# quadrotor.net
KiCad netlist of a schematic drawn in EAGLE
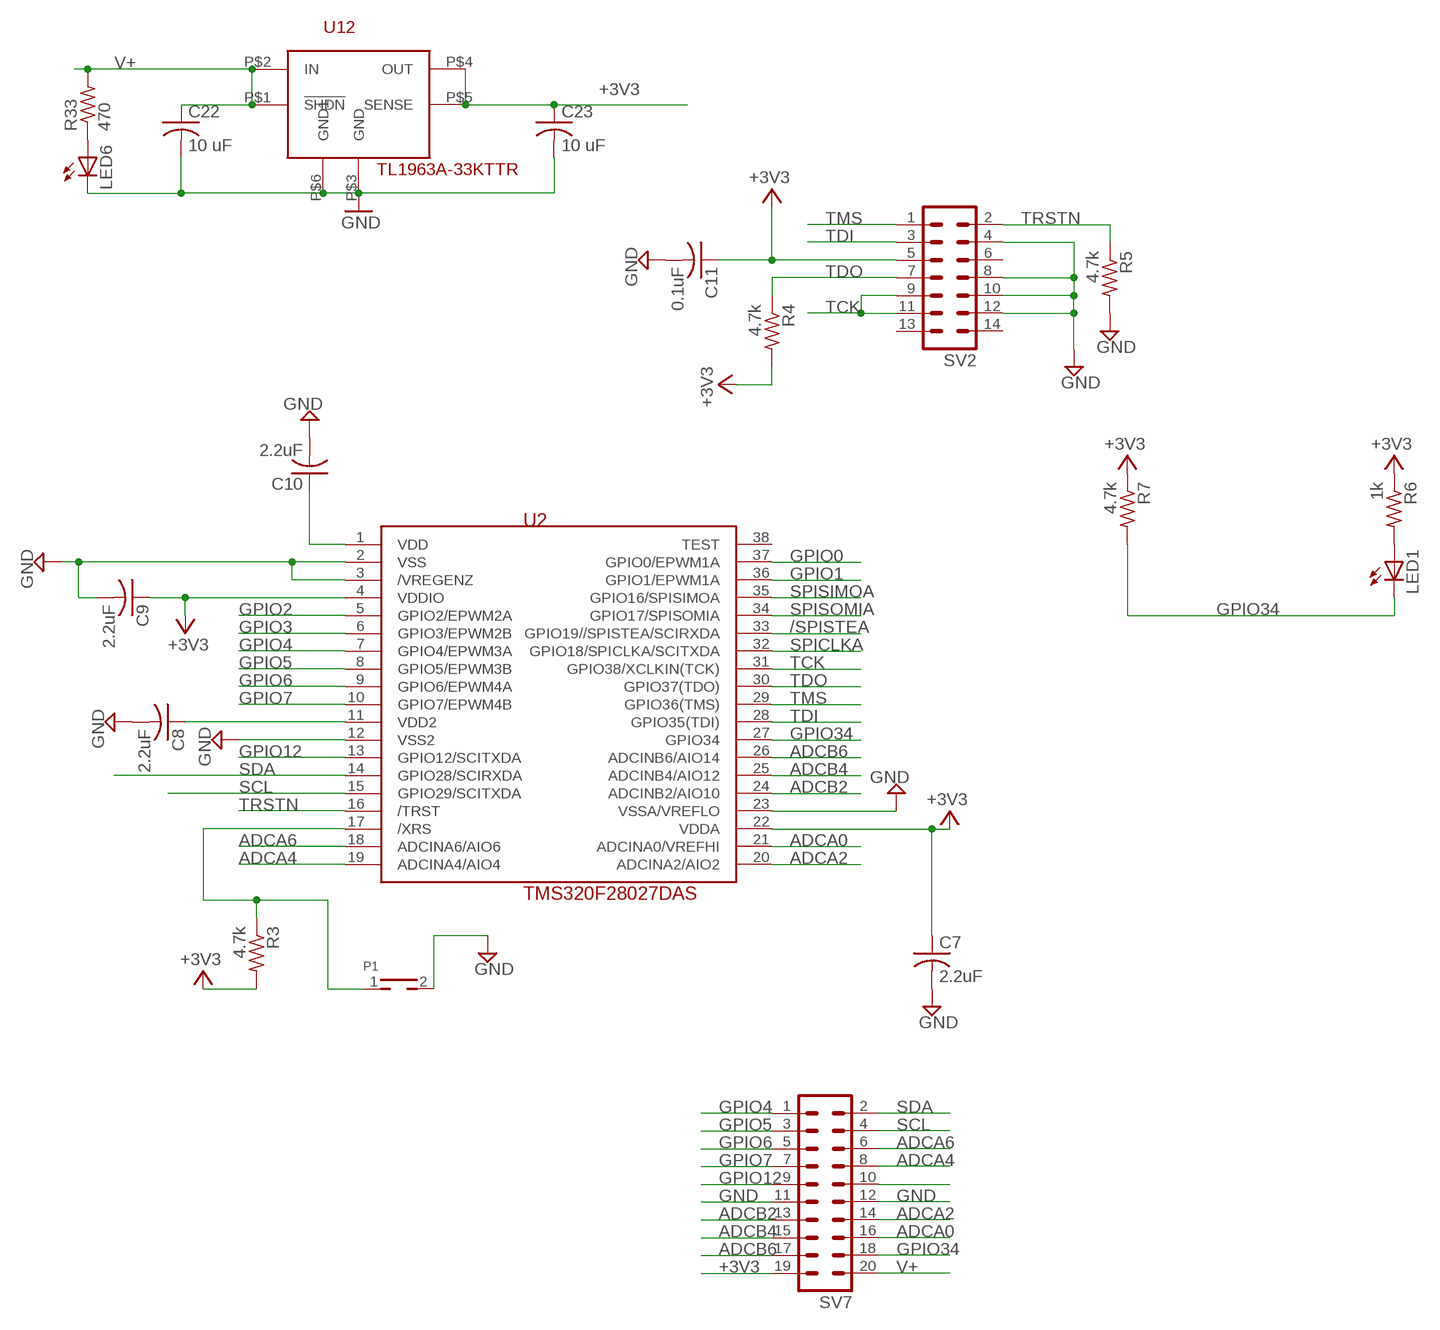
[diagram p0: schematic, sheet 1, part 1 of 2]
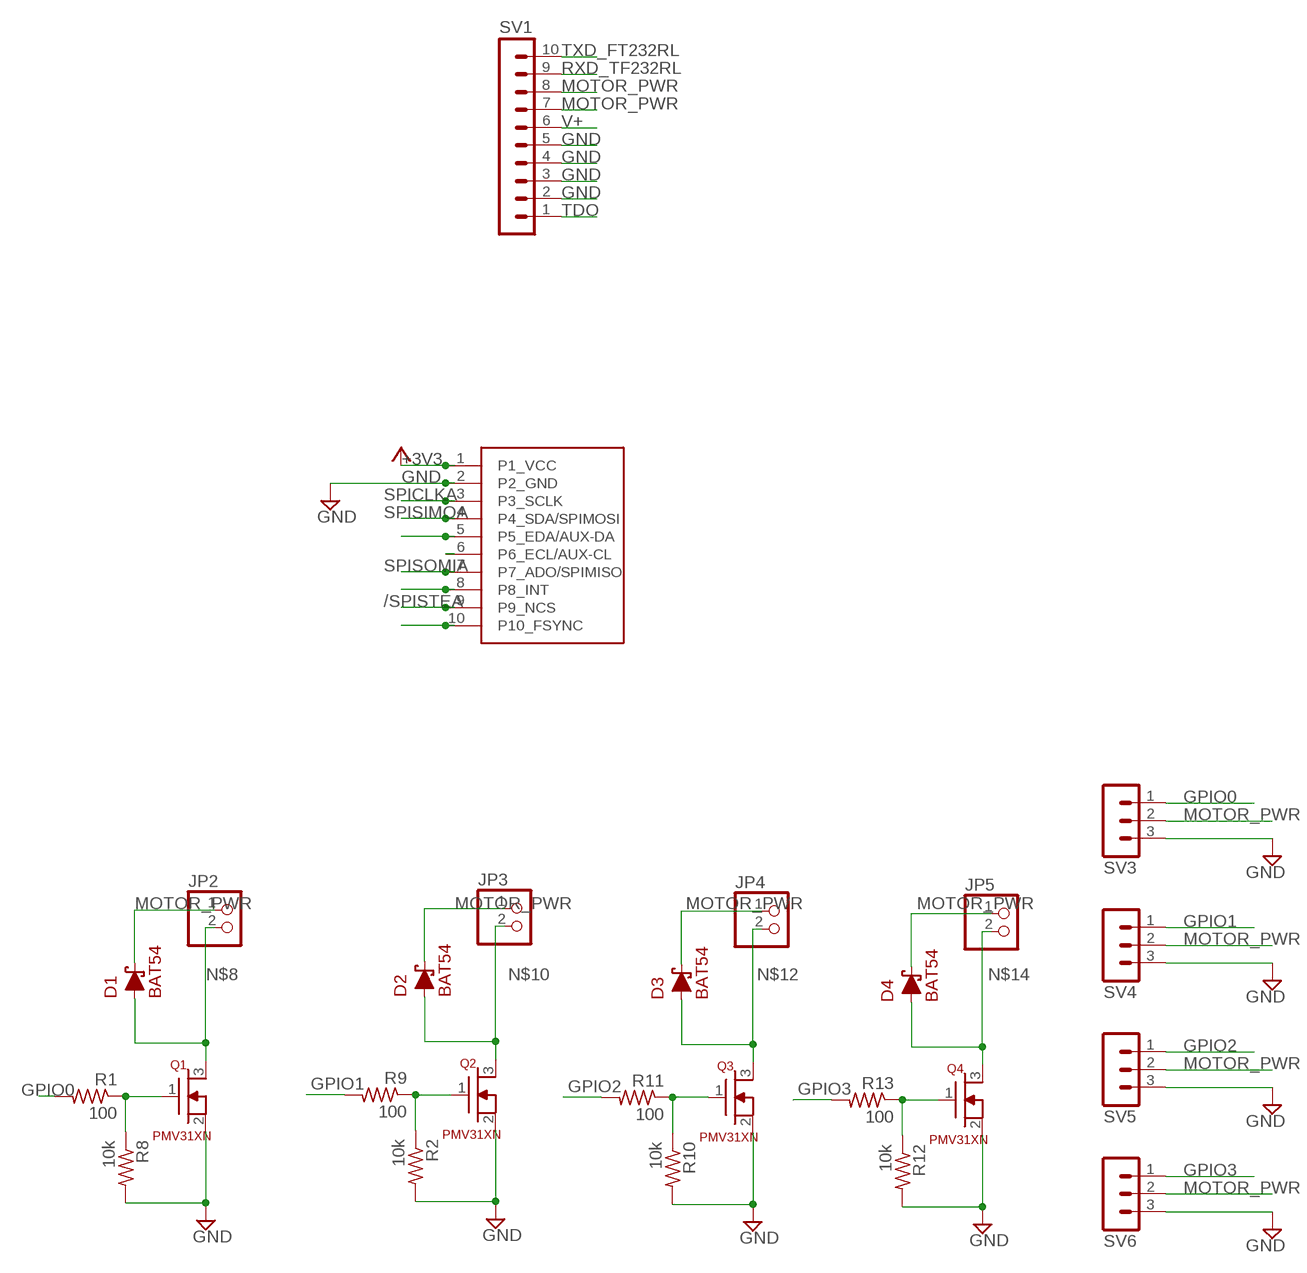
[diagram p1: schematic, sheet 1, part 2 of 2]

(export (version "E")
  (design (tool "Eeschema 10.0.6"))
  (components
    (comp (ref "C7")
      (value "2.2uF")
      (footprint "eagle-import:C1206")
      (libsource (lib "eagle-import") (part "C-USC1206"))
    )
    (comp (ref "C8")
      (value "2.2uF")
      (footprint "eagle-import:C1206")
      (libsource (lib "eagle-import") (part "C-USC1206"))
    )
    (comp (ref "C9")
      (value "2.2uF")
      (footprint "eagle-import:C1206")
      (libsource (lib "eagle-import") (part "C-USC1206"))
    )
    (comp (ref "C10")
      (value "2.2uF")
      (footprint "eagle-import:C1206")
      (libsource (lib "eagle-import") (part "C-USC1206"))
    )
    (comp (ref "C11")
      (value "0.1uF")
      (footprint "eagle-import:C1206")
      (libsource (lib "eagle-import") (part "C-USC1206"))
    )
    (comp (ref "C22")
      (value "10 uF")
      (footprint "eagle-import:C1206")
      (libsource (lib "eagle-import") (part "C-USC1206"))
    )
    (comp (ref "C23")
      (value "10 uF")
      (footprint "eagle-import:C1206")
      (libsource (lib "eagle-import") (part "C-USC1206"))
    )
    (comp (ref "D1")
      (value "BAT54")
      (footprint "eagle-import:SOT23")
      (libsource (lib "eagle-import") (part "BAT54"))
    )
    (comp (ref "D2")
      (value "BAT54")
      (footprint "eagle-import:SOT23")
      (libsource (lib "eagle-import") (part "BAT54"))
    )
    (comp (ref "D3")
      (value "BAT54")
      (footprint "eagle-import:SOT23")
      (libsource (lib "eagle-import") (part "BAT54"))
    )
    (comp (ref "D4")
      (value "BAT54")
      (footprint "eagle-import:SOT23")
      (libsource (lib "eagle-import") (part "BAT54"))
    )
    (comp (ref "JP2")
      (value "PINHD-1X2")
      (footprint "eagle-import:1X02")
      (libsource (lib "eagle-import") (part "PINHD-1X2"))
    )
    (comp (ref "JP3")
      (value "PINHD-1X2")
      (footprint "eagle-import:1X02")
      (libsource (lib "eagle-import") (part "PINHD-1X2"))
    )
    (comp (ref "JP4")
      (value "PINHD-1X2")
      (footprint "eagle-import:1X02")
      (libsource (lib "eagle-import") (part "PINHD-1X2"))
    )
    (comp (ref "JP5")
      (value "PINHD-1X2")
      (footprint "eagle-import:1X02")
      (libsource (lib "eagle-import") (part "PINHD-1X2"))
    )
    (comp (ref "LED1")
      (value "LEDCHIPLED_1206")
      (footprint "eagle-import:CHIPLED_1206")
      (libsource (lib "eagle-import") (part "LEDCHIPLED_1206"))
    )
    (comp (ref "LED6")
      (value "LEDCHIPLED_1206")
      (footprint "eagle-import:CHIPLED_1206")
      (libsource (lib "eagle-import") (part "LEDCHIPLED_1206"))
    )
    (comp (ref "P1")
      (value "TH_PUSHBOTTON")
      (footprint "eagle-import:TH_PUSHBUTTON")
      (libsource (lib "eagle-import") (part "TH_PUSHBOTTON"))
    )
    (comp (ref "Q1")
      (value "PMV31XN")
      (footprint "eagle-import:SOT23")
      (libsource (lib "eagle-import") (part "PMV31XN"))
    )
    (comp (ref "Q2")
      (value "PMV31XN")
      (footprint "eagle-import:SOT23")
      (libsource (lib "eagle-import") (part "PMV31XN"))
    )
    (comp (ref "Q3")
      (value "PMV31XN")
      (footprint "eagle-import:SOT23")
      (libsource (lib "eagle-import") (part "PMV31XN"))
    )
    (comp (ref "Q4")
      (value "PMV31XN")
      (footprint "eagle-import:SOT23")
      (libsource (lib "eagle-import") (part "PMV31XN"))
    )
    (comp (ref "R1")
      (value "100")
      (footprint "eagle-import:R1206")
      (libsource (lib "eagle-import") (part "R-US_R1206"))
    )
    (comp (ref "R2")
      (value "10k")
      (footprint "eagle-import:R1206")
      (libsource (lib "eagle-import") (part "R-US_R1206"))
    )
    (comp (ref "R3")
      (value "4.7k")
      (footprint "eagle-import:R1206")
      (libsource (lib "eagle-import") (part "R-US_R1206"))
    )
    (comp (ref "R4")
      (value "4.7k")
      (footprint "eagle-import:R1206")
      (libsource (lib "eagle-import") (part "R-US_R1206"))
    )
    (comp (ref "R5")
      (value "4.7k")
      (footprint "eagle-import:R1206")
      (libsource (lib "eagle-import") (part "R-US_R1206"))
    )
    (comp (ref "R6")
      (value "1k")
      (footprint "eagle-import:R1206")
      (libsource (lib "eagle-import") (part "R-US_R1206"))
    )
    (comp (ref "R7")
      (value "4.7k")
      (footprint "eagle-import:R1206")
      (libsource (lib "eagle-import") (part "R-US_R1206"))
    )
    (comp (ref "R8")
      (value "10k")
      (footprint "eagle-import:R1206")
      (libsource (lib "eagle-import") (part "R-US_R1206"))
    )
    (comp (ref "R9")
      (value "100")
      (footprint "eagle-import:R1206")
      (libsource (lib "eagle-import") (part "R-US_R1206"))
    )
    (comp (ref "R10")
      (value "10k")
      (footprint "eagle-import:R1206")
      (libsource (lib "eagle-import") (part "R-US_R1206"))
    )
    (comp (ref "R11")
      (value "100")
      (footprint "eagle-import:R1206")
      (libsource (lib "eagle-import") (part "R-US_R1206"))
    )
    (comp (ref "R12")
      (value "10k")
      (footprint "eagle-import:R1206")
      (libsource (lib "eagle-import") (part "R-US_R1206"))
    )
    (comp (ref "R13")
      (value "100")
      (footprint "eagle-import:R1206")
      (libsource (lib "eagle-import") (part "R-US_R1206"))
    )
    (comp (ref "R33")
      (value "470")
      (footprint "eagle-import:M1206")
      (libsource (lib "eagle-import") (part "R-US_M1206"))
    )
    (comp (ref "SV1")
      (value "MA10-1")
      (footprint "eagle-import:MA10-1")
      (libsource (lib "eagle-import") (part "MA10-1"))
    )
    (comp (ref "SV2")
      (value "MA07-2")
      (footprint "eagle-import:MA07-2")
      (libsource (lib "eagle-import") (part "MA07-2"))
    )
    (comp (ref "SV3")
      (value "MA03-1")
      (footprint "eagle-import:MA03-1")
      (libsource (lib "eagle-import") (part "MA03-1"))
    )
    (comp (ref "SV4")
      (value "MA03-1")
      (footprint "eagle-import:MA03-1")
      (libsource (lib "eagle-import") (part "MA03-1"))
    )
    (comp (ref "SV5")
      (value "MA03-1")
      (footprint "eagle-import:MA03-1")
      (libsource (lib "eagle-import") (part "MA03-1"))
    )
    (comp (ref "SV6")
      (value "MA03-1")
      (footprint "eagle-import:MA03-1")
      (libsource (lib "eagle-import") (part "MA03-1"))
    )
    (comp (ref "SV7")
      (value "MA10-2")
      (footprint "eagle-import:MA10-2")
      (libsource (lib "eagle-import") (part "MA10-2"))
    )
    (comp (ref "U$1")
      (value "MPU-9250-BB")
      (footprint "eagle-import:MPU-9250-BB")
      (libsource (lib "eagle-import") (part "MPU-9250-BB"))
    )
    (comp (ref "U2")
      (value "TMS320F28027DAS")
      (footprint "eagle-import:DA38")
      (libsource (lib "eagle-import") (part "TMS320F28027DAS"))
    )
    (comp (ref "U12")
      (value "TL1963A-33KTTR")
      (footprint "eagle-import:TL1963AKTTR")
      (libsource (lib "eagle-import") (part "TL1963A-33KTTR"))
    )
  )
  (nets
    (net (code "1") (name "+3V3") (class "Default")
      (node (ref "C11") (pin "1") (pinfunction "1_1") (pintype "passive"))
      (node (ref "C23") (pin "1") (pinfunction "1_1") (pintype "passive"))
      (node (ref "C7") (pin "1") (pinfunction "1_1") (pintype "passive"))
      (node (ref "C9") (pin "1") (pinfunction "1_1") (pintype "passive"))
      (node (ref "R3") (pin "2") (pinfunction "2_2") (pintype "passive"))
      (node (ref "R4") (pin "2") (pinfunction "2_2") (pintype "passive"))
      (node (ref "R6") (pin "1") (pinfunction "1_1") (pintype "passive"))
      (node (ref "R7") (pin "1") (pinfunction "1_1") (pintype "passive"))
      (node (ref "SV2") (pin "5") (pinfunction "5_5") (pintype "passive"))
      (node (ref "SV7") (pin "19") (pinfunction "19_19") (pintype "passive"))
      (node (ref "U$1") (pin "1") (pinfunction "P1_VCC_1") (pintype "bidirectional"))
      (node (ref "U12") (pin "P$4") (pinfunction "OUT_P$4") (pintype "bidirectional"))
      (node (ref "U12") (pin "P$5") (pinfunction "SENSE_P$5") (pintype "bidirectional"))
      (node (ref "U2") (pin "22") (pinfunction "VDDA_22") (pintype "bidirectional"))
      (node (ref "U2") (pin "4") (pinfunction "VDDIO_4") (pintype "bidirectional"))
    )
    (net (code "2") (name "/ADCA0") (class "Default")
      (node (ref "SV7") (pin "16") (pinfunction "16_16") (pintype "passive"))
      (node (ref "U2") (pin "21") (pinfunction "ADCINA0/VREFHI_21") (pintype "bidirectional"))
    )
    (net (code "3") (name "/ADCA2") (class "Default")
      (node (ref "SV7") (pin "14") (pinfunction "14_14") (pintype "passive"))
      (node (ref "U2") (pin "20") (pinfunction "ADCINA2/AIO2_20") (pintype "bidirectional"))
    )
    (net (code "4") (name "/ADCA4") (class "Default")
      (node (ref "SV7") (pin "8") (pinfunction "8_8") (pintype "passive"))
      (node (ref "U2") (pin "19") (pinfunction "ADCINA4/AIO4_19") (pintype "bidirectional"))
    )
    (net (code "5") (name "/ADCA6") (class "Default")
      (node (ref "SV7") (pin "6") (pinfunction "6_6") (pintype "passive"))
      (node (ref "U2") (pin "18") (pinfunction "ADCINA6/AIO6_18") (pintype "bidirectional"))
    )
    (net (code "6") (name "/ADCB2") (class "Default")
      (node (ref "SV7") (pin "13") (pinfunction "13_13") (pintype "passive"))
      (node (ref "U2") (pin "24") (pinfunction "ADCINB2/AIO10_24") (pintype "bidirectional"))
    )
    (net (code "7") (name "/ADCB4") (class "Default")
      (node (ref "SV7") (pin "15") (pinfunction "15_15") (pintype "passive"))
      (node (ref "U2") (pin "25") (pinfunction "ADCINB4/AIO12_25") (pintype "bidirectional"))
    )
    (net (code "8") (name "/ADCB6") (class "Default")
      (node (ref "SV7") (pin "17") (pinfunction "17_17") (pintype "passive"))
      (node (ref "U2") (pin "26") (pinfunction "ADCINB6/AIO14_26") (pintype "bidirectional"))
    )
    (net (code "9") (name "/GPIO0") (class "Default")
      (node (ref "R1") (pin "2") (pinfunction "2_2") (pintype "passive"))
      (node (ref "SV3") (pin "1") (pinfunction "1_1") (pintype "passive"))
      (node (ref "U2") (pin "37") (pinfunction "GPIO0/EPWM1A_37") (pintype "bidirectional"))
    )
    (net (code "10") (name "/GPIO1") (class "Default")
      (node (ref "R9") (pin "2") (pinfunction "2_2") (pintype "passive"))
      (node (ref "SV4") (pin "1") (pinfunction "1_1") (pintype "passive"))
      (node (ref "U2") (pin "36") (pinfunction "GPIO1/EPWM1A_36") (pintype "bidirectional"))
    )
    (net (code "11") (name "/GPIO2") (class "Default")
      (node (ref "R11") (pin "2") (pinfunction "2_2") (pintype "passive"))
      (node (ref "SV5") (pin "1") (pinfunction "1_1") (pintype "passive"))
      (node (ref "U2") (pin "5") (pinfunction "GPIO2/EPWM2A_5") (pintype "bidirectional"))
    )
    (net (code "12") (name "/GPIO3") (class "Default")
      (node (ref "R13") (pin "2") (pinfunction "2_2") (pintype "passive"))
      (node (ref "SV6") (pin "1") (pinfunction "1_1") (pintype "passive"))
      (node (ref "U2") (pin "6") (pinfunction "GPIO3/EPWM2B_6") (pintype "bidirectional"))
    )
    (net (code "13") (name "/GPIO4") (class "Default")
      (node (ref "SV7") (pin "1") (pinfunction "1_1") (pintype "passive"))
      (node (ref "U2") (pin "7") (pinfunction "GPIO4/EPWM3A_7") (pintype "bidirectional"))
    )
    (net (code "14") (name "/GPIO5") (class "Default")
      (node (ref "SV7") (pin "3") (pinfunction "3_3") (pintype "passive"))
      (node (ref "U2") (pin "8") (pinfunction "GPIO5/EPWM3B_8") (pintype "bidirectional"))
    )
    (net (code "15") (name "/GPIO6") (class "Default")
      (node (ref "SV7") (pin "5") (pinfunction "5_5") (pintype "passive"))
      (node (ref "U2") (pin "9") (pinfunction "GPIO6/EPWM4A_9") (pintype "bidirectional"))
    )
    (net (code "16") (name "/GPIO7") (class "Default")
      (node (ref "SV7") (pin "7") (pinfunction "7_7") (pintype "passive"))
      (node (ref "U2") (pin "10") (pinfunction "GPIO7/EPWM4B_10") (pintype "bidirectional"))
    )
    (net (code "17") (name "/GPIO12") (class "Default")
      (node (ref "SV7") (pin "9") (pinfunction "9_9") (pintype "passive"))
      (node (ref "U2") (pin "13") (pinfunction "GPIO12/SCITXDA_13") (pintype "bidirectional"))
    )
    (net (code "18") (name "/GPIO34") (class "Default")
      (node (ref "LED1") (pin "C") (pinfunction "C_C") (pintype "passive"))
      (node (ref "R7") (pin "2") (pinfunction "2_2") (pintype "passive"))
      (node (ref "SV7") (pin "18") (pinfunction "18_18") (pintype "passive"))
      (node (ref "U2") (pin "27") (pinfunction "GPIO34_27") (pintype "bidirectional"))
    )
    (net (code "19") (name "/MOTOR_PWR") (class "Default")
      (node (ref "D1") (pin "3") (pinfunction "3_3") (pintype "passive"))
      (node (ref "D2") (pin "3") (pinfunction "3_3") (pintype "passive"))
      (node (ref "D3") (pin "3") (pinfunction "3_3") (pintype "passive"))
      (node (ref "D4") (pin "3") (pinfunction "3_3") (pintype "passive"))
      (node (ref "JP2") (pin "1") (pinfunction "1_1") (pintype "passive"))
      (node (ref "JP3") (pin "1") (pinfunction "1_1") (pintype "passive"))
      (node (ref "JP4") (pin "1") (pinfunction "1_1") (pintype "passive"))
      (node (ref "JP5") (pin "1") (pinfunction "1_1") (pintype "passive"))
      (node (ref "SV1") (pin "7") (pinfunction "7_7") (pintype "passive"))
      (node (ref "SV1") (pin "8") (pinfunction "8_8") (pintype "passive"))
      (node (ref "SV3") (pin "2") (pinfunction "2_2") (pintype "passive"))
      (node (ref "SV4") (pin "2") (pinfunction "2_2") (pintype "passive"))
      (node (ref "SV5") (pin "2") (pinfunction "2_2") (pintype "passive"))
      (node (ref "SV6") (pin "2") (pinfunction "2_2") (pintype "passive"))
    )
    (net (code "20") (name "/N$8") (class "Default")
      (node (ref "D1") (pin "1") (pinfunction "1_1") (pintype "passive"))
      (node (ref "JP2") (pin "2") (pinfunction "2_2") (pintype "passive"))
      (node (ref "Q1") (pin "3") (pinfunction "D_3") (pintype "passive"))
    )
    (net (code "21") (name "/N$10") (class "Default")
      (node (ref "D2") (pin "1") (pinfunction "1_1") (pintype "passive"))
      (node (ref "JP3") (pin "2") (pinfunction "2_2") (pintype "passive"))
      (node (ref "Q2") (pin "3") (pinfunction "D_3") (pintype "passive"))
    )
    (net (code "22") (name "/N$12") (class "Default")
      (node (ref "D3") (pin "1") (pinfunction "1_1") (pintype "passive"))
      (node (ref "JP4") (pin "2") (pinfunction "2_2") (pintype "passive"))
      (node (ref "Q3") (pin "3") (pinfunction "D_3") (pintype "passive"))
    )
    (net (code "23") (name "/N$14") (class "Default")
      (node (ref "D4") (pin "1") (pinfunction "1_1") (pintype "passive"))
      (node (ref "JP5") (pin "2") (pinfunction "2_2") (pintype "passive"))
      (node (ref "Q4") (pin "3") (pinfunction "D_3") (pintype "passive"))
    )
    (net (code "24") (name "/RXD_TF232RL") (class "Default")
      (node (ref "SV1") (pin "9") (pinfunction "9_9") (pintype "passive"))
    )
    (net (code "25") (name "/SCL") (class "Default")
      (node (ref "SV7") (pin "4") (pinfunction "4_4") (pintype "passive"))
      (node (ref "U2") (pin "15") (pinfunction "GPIO29/SCITXDA_15") (pintype "bidirectional"))
    )
    (net (code "26") (name "/SDA") (class "Default")
      (node (ref "SV7") (pin "2") (pinfunction "2_2") (pintype "passive"))
      (node (ref "U2") (pin "14") (pinfunction "GPIO28/SCIRXDA_14") (pintype "bidirectional"))
    )
    (net (code "27") (name "/SPICLKA") (class "Default")
      (node (ref "U$1") (pin "3") (pinfunction "P3_SCLK_3") (pintype "bidirectional"))
      (node (ref "U2") (pin "32") (pinfunction "GPIO18/SPICLKA/SCITXDA_32") (pintype "bidirectional"))
    )
    (net (code "28") (name "/SPISIMOA") (class "Default")
      (node (ref "U$1") (pin "4") (pinfunction "P4_SDA/SPIMOSI_4") (pintype "bidirectional"))
      (node (ref "U2") (pin "35") (pinfunction "GPIO16/SPISIMOA_35") (pintype "bidirectional"))
    )
    (net (code "29") (name "/SPISOMIA") (class "Default")
      (node (ref "U$1") (pin "7") (pinfunction "P7_ADO/SPIMISO_7") (pintype "bidirectional"))
      (node (ref "U2") (pin "34") (pinfunction "GPIO17/SPISOMIA_34") (pintype "bidirectional"))
    )
    (net (code "30") (name "/TCK") (class "Default")
      (node (ref "SV2") (pin "11") (pinfunction "11_11") (pintype "passive"))
      (node (ref "SV2") (pin "9") (pinfunction "9_9") (pintype "passive"))
      (node (ref "U2") (pin "31") (pinfunction "GPIO38/XCLKIN(TCK)_31") (pintype "bidirectional"))
    )
    (net (code "31") (name "/TDI") (class "Default")
      (node (ref "SV2") (pin "3") (pinfunction "3_3") (pintype "passive"))
      (node (ref "U2") (pin "28") (pinfunction "GPIO35(TDI)_28") (pintype "bidirectional"))
    )
    (net (code "32") (name "/TDO") (class "Default")
      (node (ref "R4") (pin "1") (pinfunction "1_1") (pintype "passive"))
      (node (ref "SV1") (pin "1") (pinfunction "1_1") (pintype "passive"))
      (node (ref "SV2") (pin "7") (pinfunction "7_7") (pintype "passive"))
      (node (ref "U2") (pin "30") (pinfunction "GPIO37(TDO)_30") (pintype "bidirectional"))
    )
    (net (code "33") (name "/TMS") (class "Default")
      (node (ref "SV2") (pin "1") (pinfunction "1_1") (pintype "passive"))
      (node (ref "U2") (pin "29") (pinfunction "GPIO36(TMS)_29") (pintype "bidirectional"))
    )
    (net (code "34") (name "/TRSTN") (class "Default")
      (node (ref "R5") (pin "1") (pinfunction "1_1") (pintype "passive"))
      (node (ref "SV2") (pin "2") (pinfunction "2_2") (pintype "passive"))
      (node (ref "U2") (pin "16") (pinfunction "/TRST_16") (pintype "bidirectional"))
    )
    (net (code "35") (name "/TXD_FT232RL") (class "Default")
      (node (ref "SV1") (pin "10") (pinfunction "10_10") (pintype "passive"))
    )
    (net (code "36") (name "/V+") (class "Default")
      (node (ref "C22") (pin "1") (pinfunction "1_1") (pintype "passive"))
      (node (ref "R33") (pin "2") (pinfunction "2_2") (pintype "passive"))
      (node (ref "SV1") (pin "6") (pinfunction "6_6") (pintype "passive"))
      (node (ref "SV7") (pin "20") (pinfunction "20_20") (pintype "passive"))
      (node (ref "U12") (pin "P$1") (pinfunction "~{SHDN}_P$1") (pintype "bidirectional"))
      (node (ref "U12") (pin "P$2") (pinfunction "IN_P$2") (pintype "bidirectional"))
    )
    (net (code "37") (name "/{slash}SPISTEA") (class "Default")
      (node (ref "U$1") (pin "9") (pinfunction "P9_NCS_9") (pintype "bidirectional"))
      (node (ref "U2") (pin "33") (pinfunction "GPIO19//SPISTEA/SCIRXDA_33") (pintype "bidirectional"))
    )
    (net (code "38") (name "GND") (class "Default")
      (node (ref "C10") (pin "2") (pinfunction "2_2") (pintype "passive"))
      (node (ref "C11") (pin "2") (pinfunction "2_2") (pintype "passive"))
      (node (ref "C22") (pin "2") (pinfunction "2_2") (pintype "passive"))
      (node (ref "C23") (pin "2") (pinfunction "2_2") (pintype "passive"))
      (node (ref "C7") (pin "2") (pinfunction "2_2") (pintype "passive"))
      (node (ref "C8") (pin "2") (pinfunction "2_2") (pintype "passive"))
      (node (ref "C9") (pin "2") (pinfunction "2_2") (pintype "passive"))
      (node (ref "LED6") (pin "C") (pinfunction "C_C") (pintype "passive"))
      (node (ref "P1") (pin "2") (pinfunction "2_2") (pintype "bidirectional"))
      (node (ref "Q1") (pin "2") (pinfunction "S_2") (pintype "passive"))
      (node (ref "Q2") (pin "2") (pinfunction "S_2") (pintype "passive"))
      (node (ref "Q3") (pin "2") (pinfunction "S_2") (pintype "passive"))
      (node (ref "Q4") (pin "2") (pinfunction "S_2") (pintype "passive"))
      (node (ref "R10") (pin "2") (pinfunction "2_2") (pintype "passive"))
      (node (ref "R12") (pin "2") (pinfunction "2_2") (pintype "passive"))
      (node (ref "R2") (pin "2") (pinfunction "2_2") (pintype "passive"))
      (node (ref "R5") (pin "2") (pinfunction "2_2") (pintype "passive"))
      (node (ref "R8") (pin "2") (pinfunction "2_2") (pintype "passive"))
      (node (ref "SV1") (pin "2") (pinfunction "2_2") (pintype "passive"))
      (node (ref "SV1") (pin "3") (pinfunction "3_3") (pintype "passive"))
      (node (ref "SV1") (pin "4") (pinfunction "4_4") (pintype "passive"))
      (node (ref "SV1") (pin "5") (pinfunction "5_5") (pintype "passive"))
      (node (ref "SV2") (pin "10") (pinfunction "10_10") (pintype "passive"))
      (node (ref "SV2") (pin "12") (pinfunction "12_12") (pintype "passive"))
      (node (ref "SV2") (pin "4") (pinfunction "4_4") (pintype "passive"))
      (node (ref "SV2") (pin "8") (pinfunction "8_8") (pintype "passive"))
      (node (ref "SV3") (pin "3") (pinfunction "3_3") (pintype "passive"))
      (node (ref "SV4") (pin "3") (pinfunction "3_3") (pintype "passive"))
      (node (ref "SV5") (pin "3") (pinfunction "3_3") (pintype "passive"))
      (node (ref "SV6") (pin "3") (pinfunction "3_3") (pintype "passive"))
      (node (ref "SV7") (pin "11") (pinfunction "11_11") (pintype "passive"))
      (node (ref "SV7") (pin "12") (pinfunction "12_12") (pintype "passive"))
      (node (ref "U$1") (pin "2") (pinfunction "P2_GND_2") (pintype "bidirectional"))
      (node (ref "U12") (pin "P$3") (pinfunction "GND_P$3") (pintype "bidirectional"))
      (node (ref "U12") (pin "P$6") (pinfunction "GND1_P$6") (pintype "bidirectional"))
      (node (ref "U2") (pin "12") (pinfunction "VSS2_12") (pintype "bidirectional"))
      (node (ref "U2") (pin "2") (pinfunction "VSS_2") (pintype "bidirectional"))
      (node (ref "U2") (pin "23") (pinfunction "VSSA/VREFLO_23") (pintype "bidirectional"))
      (node (ref "U2") (pin "3") (pinfunction "/VREGENZ_3") (pintype "bidirectional"))
    )
    (net (code "39") (name "Net-(LED1-PadA)") (class "Default")
      (node (ref "LED1") (pin "A") (pinfunction "A_A") (pintype "passive"))
      (node (ref "R6") (pin "2") (pinfunction "2_2") (pintype "passive"))
    )
    (net (code "40") (name "Net-(LED6-PadA)") (class "Default")
      (node (ref "LED6") (pin "A") (pinfunction "A_A") (pintype "passive"))
      (node (ref "R33") (pin "1") (pinfunction "1_1") (pintype "passive"))
    )
    (net (code "41") (name "Net-(Q1-G)") (class "Default")
      (node (ref "Q1") (pin "1") (pinfunction "G_1") (pintype "passive"))
      (node (ref "R1") (pin "1") (pinfunction "1_1") (pintype "passive"))
      (node (ref "R8") (pin "1") (pinfunction "1_1") (pintype "passive"))
    )
    (net (code "42") (name "Net-(Q2-G)") (class "Default")
      (node (ref "Q2") (pin "1") (pinfunction "G_1") (pintype "passive"))
      (node (ref "R2") (pin "1") (pinfunction "1_1") (pintype "passive"))
      (node (ref "R9") (pin "1") (pinfunction "1_1") (pintype "passive"))
    )
    (net (code "43") (name "Net-(Q3-G)") (class "Default")
      (node (ref "Q3") (pin "1") (pinfunction "G_1") (pintype "passive"))
      (node (ref "R10") (pin "1") (pinfunction "1_1") (pintype "passive"))
      (node (ref "R11") (pin "1") (pinfunction "1_1") (pintype "passive"))
    )
    (net (code "44") (name "Net-(Q4-G)") (class "Default")
      (node (ref "Q4") (pin "1") (pinfunction "G_1") (pintype "passive"))
      (node (ref "R12") (pin "1") (pinfunction "1_1") (pintype "passive"))
      (node (ref "R13") (pin "1") (pinfunction "1_1") (pintype "passive"))
    )
    (net (code "45") (name "Net-(U2-VDD)") (class "Default")
      (node (ref "C10") (pin "1") (pinfunction "1_1") (pintype "passive"))
      (node (ref "U2") (pin "1") (pinfunction "VDD_1") (pintype "bidirectional"))
    )
    (net (code "46") (name "Net-(U2-VDD2)") (class "Default")
      (node (ref "C8") (pin "1") (pinfunction "1_1") (pintype "passive"))
      (node (ref "U2") (pin "11") (pinfunction "VDD2_11") (pintype "bidirectional"))
    )
    (net (code "47") (name "Net-(U2-{slash}XRS)") (class "Default")
      (node (ref "P1") (pin "1") (pinfunction "1_1") (pintype "bidirectional"))
      (node (ref "R3") (pin "1") (pinfunction "1_1") (pintype "passive"))
      (node (ref "U2") (pin "17") (pinfunction "/XRS_17") (pintype "bidirectional"))
    )
    (net (code "48") (name "unconnected-(SV2-Pad6)") (class "Default")
      (node (ref "SV2") (pin "6") (pinfunction "6_6") (pintype "passive"))
    )
    (net (code "49") (name "unconnected-(SV2-Pad13)") (class "Default")
      (node (ref "SV2") (pin "13") (pinfunction "13_13") (pintype "passive"))
    )
    (net (code "50") (name "unconnected-(SV2-Pad14)") (class "Default")
      (node (ref "SV2") (pin "14") (pinfunction "14_14") (pintype "passive"))
    )
    (net (code "51") (name "unconnected-(SV7-Pad10)") (class "Default")
      (node (ref "SV7") (pin "10") (pinfunction "10_10") (pintype "passive"))
    )
    (net (code "52") (name "unconnected-(U$1-P5_EDA{slash}AUX-DA-Pad5)") (class "Default")
      (node (ref "U$1") (pin "5") (pinfunction "P5_EDA/AUX-DA_5") (pintype "bidirectional"))
    )
    (net (code "53") (name "unconnected-(U$1-P6_ECL{slash}AUX-CL-Pad6)") (class "Default")
      (node (ref "U$1") (pin "6") (pinfunction "P6_ECL/AUX-CL_6") (pintype "bidirectional"))
    )
    (net (code "54") (name "unconnected-(U$1-P8_INT-Pad8)") (class "Default")
      (node (ref "U$1") (pin "8") (pinfunction "P8_INT_8") (pintype "bidirectional"))
    )
    (net (code "55") (name "unconnected-(U$1-P10_FSYNC-Pad10)") (class "Default")
      (node (ref "U$1") (pin "10") (pinfunction "P10_FSYNC_10") (pintype "bidirectional"))
    )
    (net (code "56") (name "unconnected-(U2-TEST-Pad38)") (class "Default")
      (node (ref "U2") (pin "38") (pinfunction "TEST_38") (pintype "bidirectional"))
    )
  )
)
